# chickenFlap.net
KiCad netlist of a schematic drawn in Altium Designer
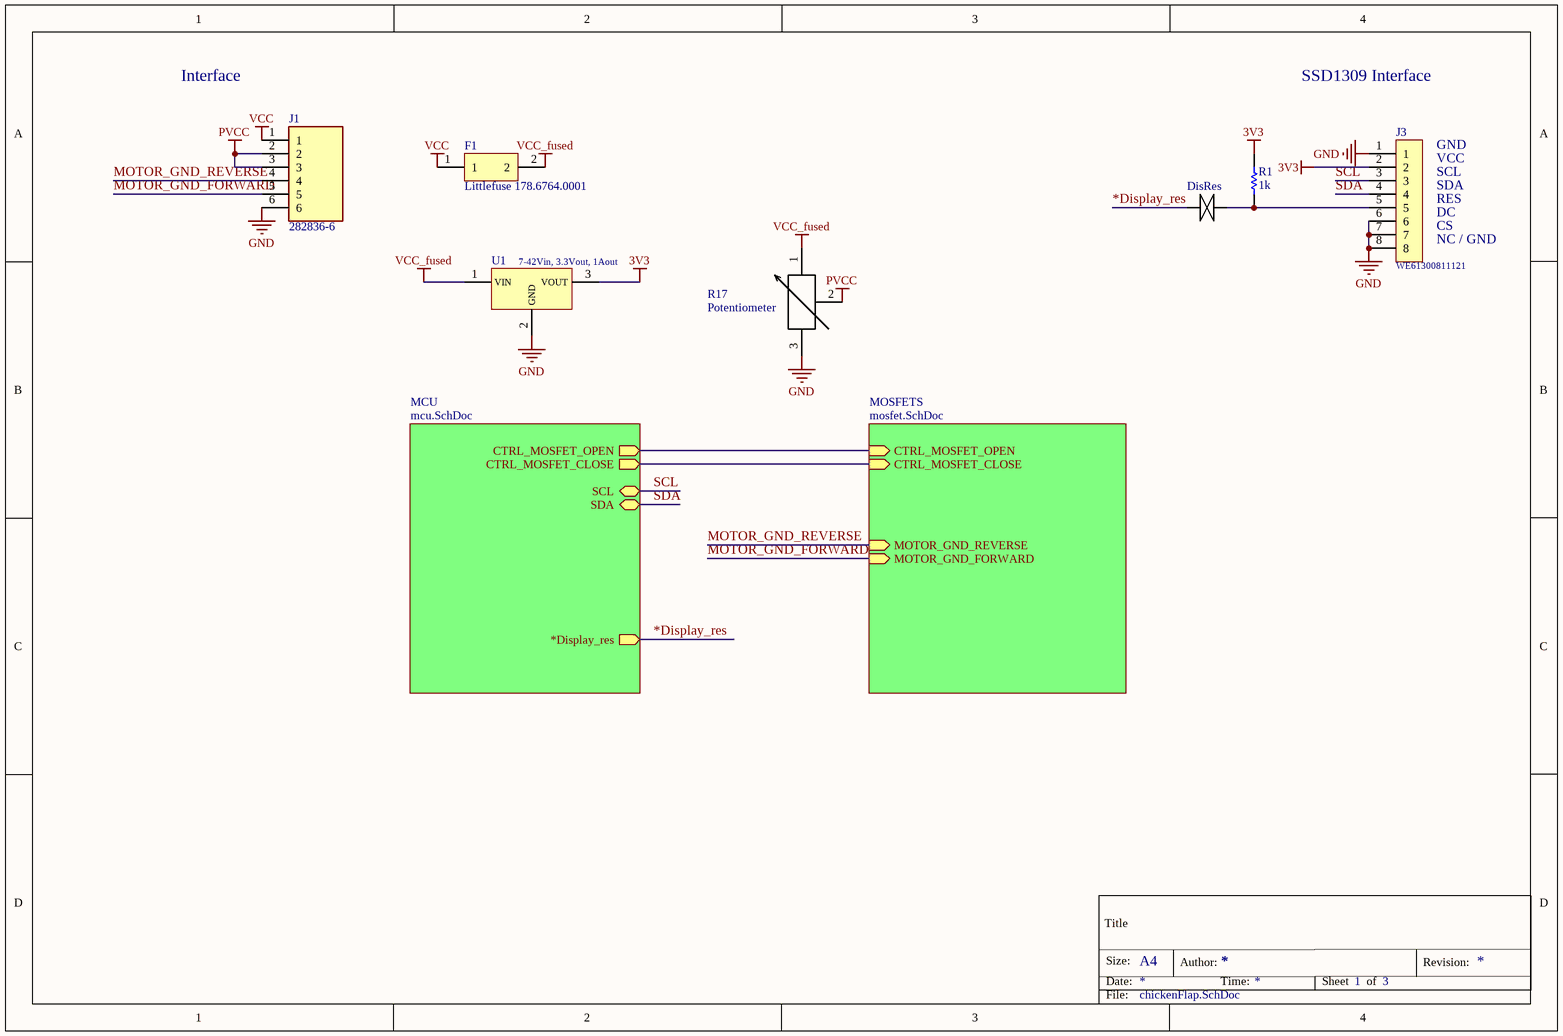
[diagram p0: chickenFlap.SchDoc]

(export (version "E")
  (design (tool "Eeschema 10.0.6"))
  (components
    (comp (ref "DisRes")
      (value "DisRes")
      (footprint "JUMPER_SINGLE_SMALL")
      (description "2 pads which can be connected truth soldering")
      (libsource (lib "connectors") (part "JUMPER_SINGLE"))
    )
    (comp (ref "F1")
      (value "Littlefuse 178.6764.0001")
      (footprint "MINI/FK1")
      (libsource (lib "fuses") (part "Fuse Mini/FK1"))
    )
    (comp (ref "J1")
      (value "282836-6")
      (footprint "SamacSys:2828366")
      (description "Connector")
      (fields (field (name "MOUSER PART NUMBER") "571-2828366"))
      (libsource (lib "*") (part "282836-6"))
    )
    (comp (ref "J3")
      (value "WE61300811121")
      (footprint "WE61300811121")
      (description "WR-PHD Pin Header, THT, pitch 2.54mm, Single Row, Vertical, 8pin")
      (fields (field (name "PART NUMBER") "61300811121") (field (name "PUBLISHER") "Wurth Elektronik"))
      (libsource (lib "connectors") (part "WE61300811121"))
    )
    (comp (ref "R1")
      (value "1k")
      (footprint "RES0603")
      (description "Chip Resistor 0603, Body 1.6x0.8mm, IPC Medium Density")
      (libsource (lib "resistors") (part "Resistor 0603"))
    )
    (comp (ref "R17")
      (value "Potentiometer")
      (footprint "Potentiometer")
      (libsource (lib "Schlib") (part "Potentiometer"))
    )
    (comp (ref "U1")
      (value "7-42Vin, 3.3Vout, 1Aout")
      (footprint "MagI³C-FDSM_SIP-3_173010x42")
      (description "MagI³C-FDSM Fixed Step Down Regulator Module, THT, SIP-3, 7-42Vin, 3.3Vout, 1Aout")
      (fields (field (name "PART NUMBER") "173010342") (field (name "PUBLISHER") "Wurth Elektronik"))
      (libsource (lib "ic_power") (part "WE173010342"))
    )
  )
  (nets
    (net (code "1") (name "/*Display_res") (class "Default")
      (node (ref "DisRes") (pin "2") (pinfunction "B_2") (pintype "passive"))
    )
    (net (code "4") (name "/MOTOR_GND_FORWARD") (class "Default")
      (node (ref "J1") (pin "5") (pinfunction "5_5") (pintype "passive"))
    )
    (net (code "5") (name "/MOTOR_GND_REVERSE") (class "Default")
      (node (ref "J1") (pin "4") (pinfunction "4_4") (pintype "passive"))
    )
    (net (code "6") (name "/SCL") (class "Default")
      (node (ref "J3") (pin "3") (pinfunction "3_3") (pintype "passive"))
    )
    (net (code "7") (name "/SDA") (class "Default")
      (node (ref "J3") (pin "4") (pinfunction "4_4") (pintype "passive"))
    )
    (net (code "8") (name "3V3") (class "Default")
      (node (ref "J3") (pin "2") (pinfunction "2_2") (pintype "passive"))
      (node (ref "R1") (pin "2") (pinfunction "2_2") (pintype "passive"))
      (node (ref "U1") (pin "3") (pinfunction "VOUT_3") (pintype "passive"))
    )
    (net (code "9") (name "GND") (class "Default")
      (node (ref "J1") (pin "6") (pinfunction "6_6") (pintype "passive"))
      (node (ref "J3") (pin "1") (pinfunction "1_1") (pintype "passive"))
      (node (ref "J3") (pin "6") (pinfunction "6_6") (pintype "passive"))
      (node (ref "J3") (pin "7") (pinfunction "7_7") (pintype "passive"))
      (node (ref "J3") (pin "8") (pinfunction "8_8") (pintype "passive"))
      (node (ref "R17") (pin "3") (pinfunction "3_3") (pintype "passive"))
      (node (ref "U1") (pin "2") (pinfunction "GND_2") (pintype "passive"))
    )
    (net (code "10") (name "Net-(DisRes-A)") (class "Default")
      (node (ref "DisRes") (pin "1") (pinfunction "A_1") (pintype "passive"))
      (node (ref "J3") (pin "5") (pinfunction "5_5") (pintype "passive"))
      (node (ref "R1") (pin "1") (pinfunction "1_1") (pintype "passive"))
    )
    (net (code "11") (name "PVCC") (class "Default")
      (node (ref "J1") (pin "2") (pinfunction "2_2") (pintype "passive"))
      (node (ref "J1") (pin "3") (pinfunction "3_3") (pintype "passive"))
      (node (ref "R17") (pin "2") (pinfunction "2_2") (pintype "passive"))
    )
    (net (code "12") (name "VCC") (class "Default")
      (node (ref "F1") (pin "1") (pinfunction "1_1") (pintype "passive"))
      (node (ref "J1") (pin "1") (pinfunction "1_1") (pintype "passive"))
    )
    (net (code "13") (name "VCC_fused") (class "Default")
      (node (ref "F1") (pin "2") (pinfunction "2_2") (pintype "passive"))
      (node (ref "R17") (pin "1") (pinfunction "1_1") (pintype "passive"))
      (node (ref "U1") (pin "1") (pinfunction "VIN_1") (pintype "passive"))
    )
  )
)
